# RoverWing-V4.net
KiCad netlist of a schematic drawn in EAGLE
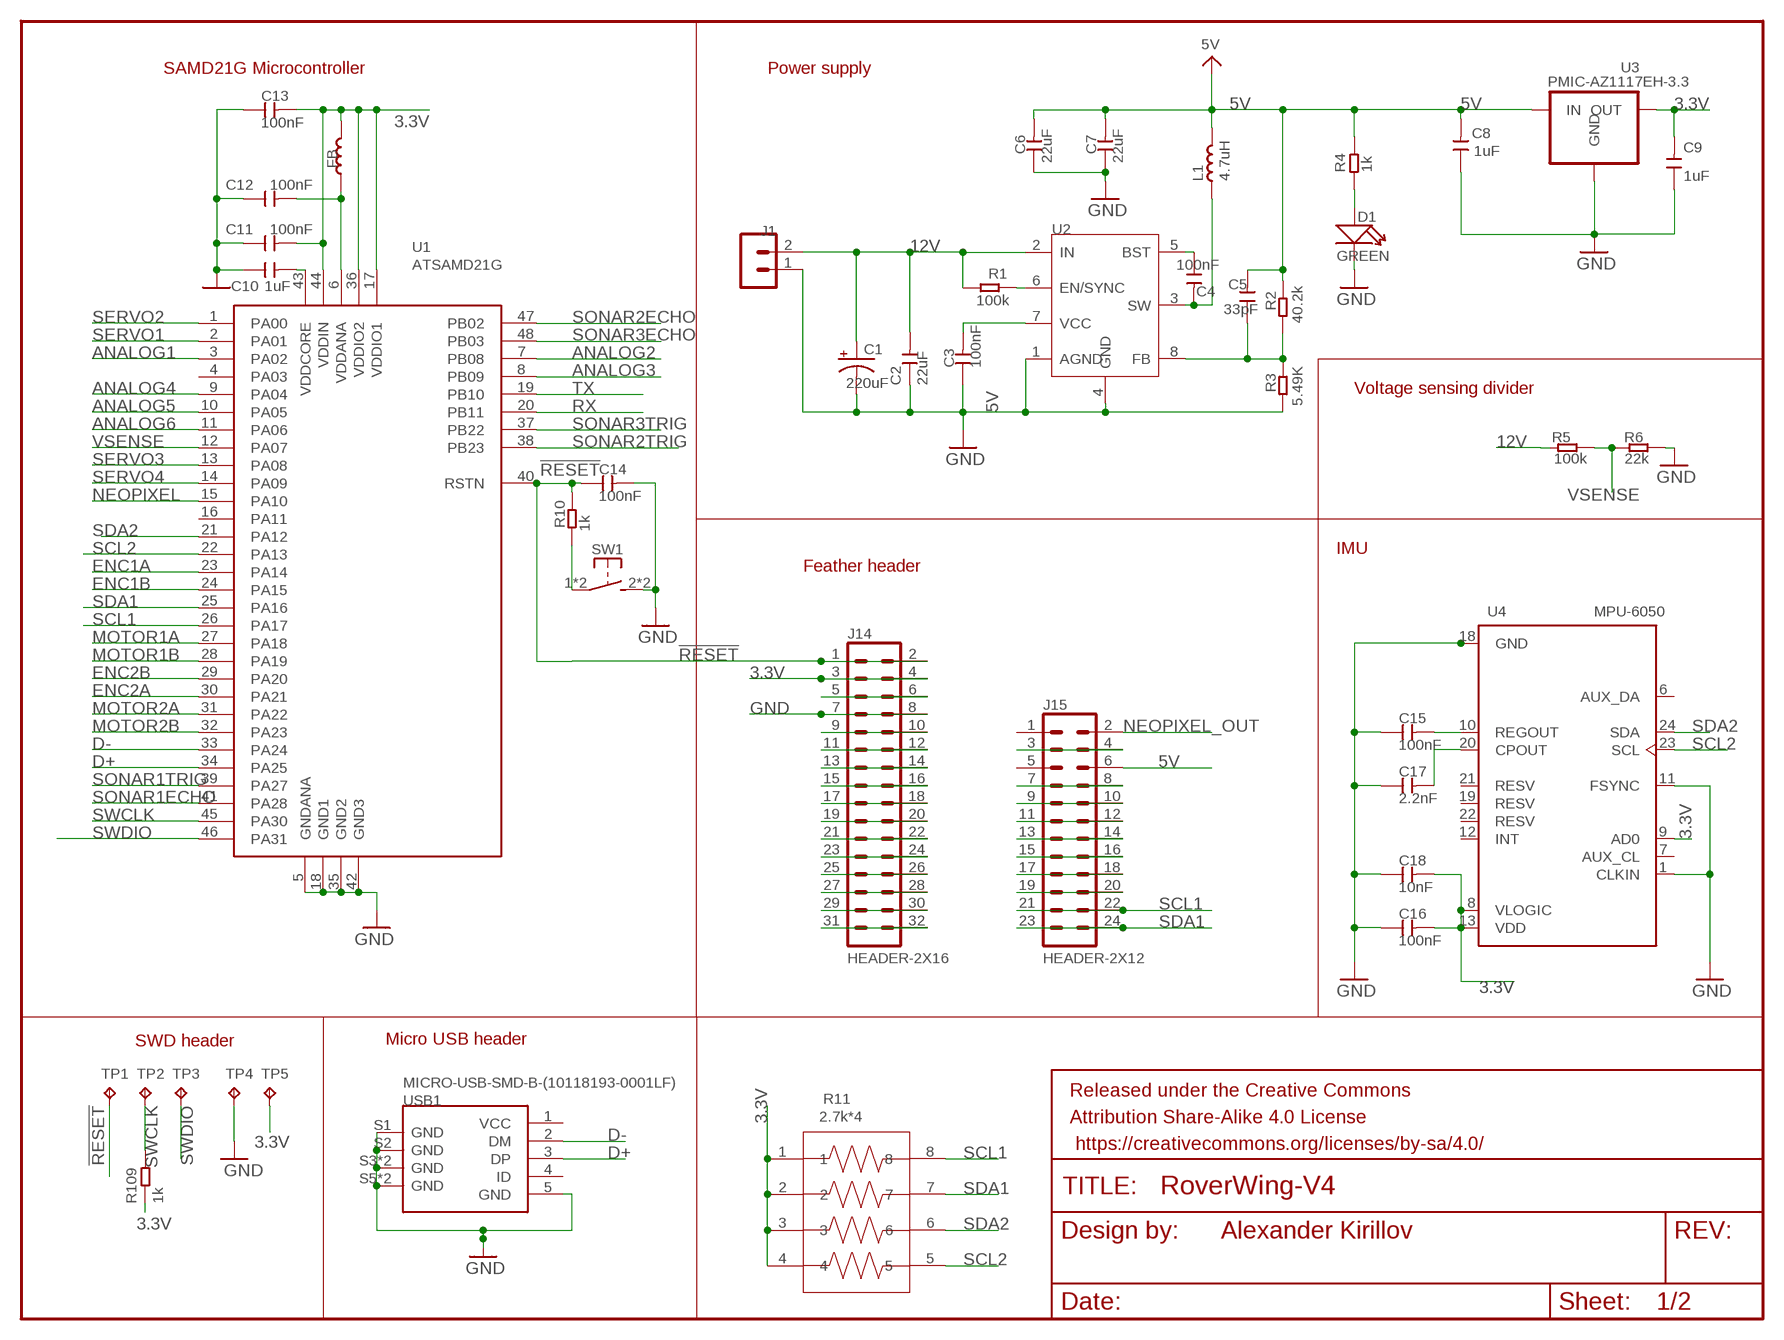
[diagram p0: schematic, sheet 1]
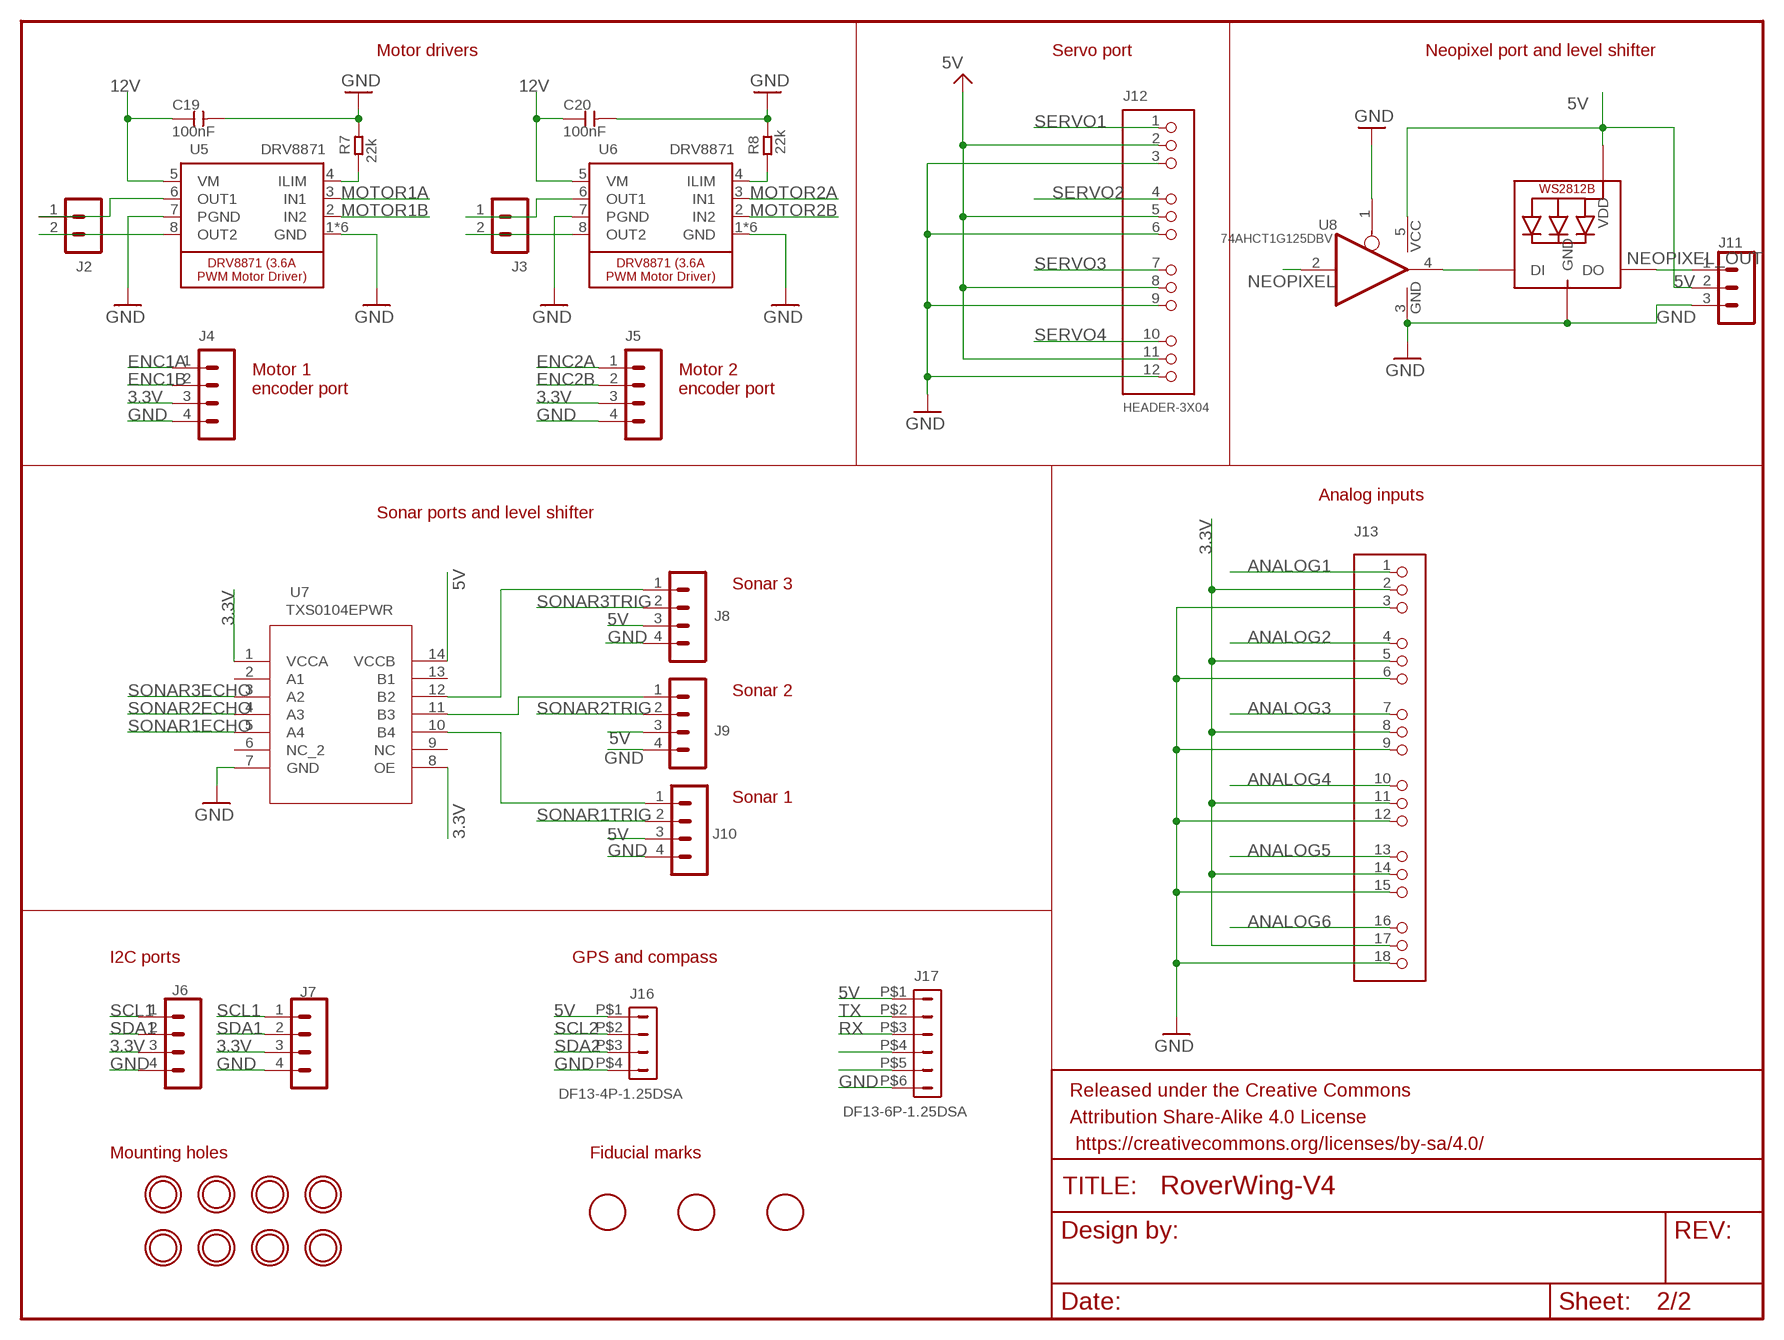
[diagram p1: schematic, sheet 2]

(export (version "E")
  (design (tool "Eeschema 10.0.6"))
  (components
    (comp (ref "C19")
      (value "100nF")
      (footprint "eagle-import:0805")
      (libsource (lib "eagle-import") (part "CAP-CERAMIC-SMD0805"))
    )
    (comp (ref "C20")
      (value "100nF")
      (footprint "eagle-import:0805")
      (libsource (lib "eagle-import") (part "CAP-CERAMIC-SMD0805"))
    )
    (comp (ref "FRAME1")
      (value "FRAME-LETTERNO_PACKAGE")
      (footprint "eagle-import:DUMMY")
      (libsource (lib "eagle-import") (part "FRAME-LETTERNO_PACKAGE"))
    )
    (comp (ref "J2")
      (value "HEADER-VH")
      (footprint "eagle-import:B2P-VH")
      (fields (field (name "PARTNO") "B2P-VH(LF)(SN)  "))
      (libsource (lib "eagle-import") (part "HEADER-VH"))
    )
    (comp (ref "J3")
      (value "HEADER-VH")
      (footprint "eagle-import:B2P-VH")
      (fields (field (name "PARTNO") "B2P-VH(LF)(SN)  "))
      (libsource (lib "eagle-import") (part "HEADER-VH"))
    )
    (comp (ref "J4")
      (value "HEADER-PH-4P")
      (footprint "eagle-import:B4B-PH-K")
      (fields (field (name "PARTNO") "B4B-PH-K-S(LF)(SN)"))
      (libsource (lib "eagle-import") (part "HEADER-PH-4P"))
    )
    (comp (ref "J5")
      (value "HEADER-PH-4P")
      (footprint "eagle-import:B4B-PH-K")
      (fields (field (name "PARTNO") "B4B-PH-K-S(LF)(SN)"))
      (libsource (lib "eagle-import") (part "HEADER-PH-4P"))
    )
    (comp (ref "J6")
      (value "HEADER-PH-4P")
      (footprint "eagle-import:B4B-PH-K")
      (fields (field (name "PARTNO") "B4B-PH-K-S(LF)(SN)"))
      (libsource (lib "eagle-import") (part "HEADER-PH-4P"))
    )
    (comp (ref "J7")
      (value "HEADER-PH-4P")
      (footprint "eagle-import:B4B-PH-K")
      (fields (field (name "PARTNO") "B4B-PH-K-S(LF)(SN)"))
      (libsource (lib "eagle-import") (part "HEADER-PH-4P"))
    )
    (comp (ref "J8")
      (value "HEADER-PH-4P")
      (footprint "eagle-import:B4B-PH-K")
      (fields (field (name "PARTNO") "B4B-PH-K-S(LF)(SN)"))
      (libsource (lib "eagle-import") (part "HEADER-PH-4P"))
    )
    (comp (ref "J9")
      (value "HEADER-PH-4P")
      (footprint "eagle-import:B4B-PH-K")
      (fields (field (name "PARTNO") "B4B-PH-K-S(LF)(SN)"))
      (libsource (lib "eagle-import") (part "HEADER-PH-4P"))
    )
    (comp (ref "J10")
      (value "HEADER-PH-4P")
      (footprint "eagle-import:B4B-PH-K")
      (fields (field (name "PARTNO") "B4B-PH-K-S(LF)(SN)"))
      (libsource (lib "eagle-import") (part "HEADER-PH-4P"))
    )
    (comp (ref "J11")
      (value "HEADER-PH-3P")
      (footprint "eagle-import:B3B-PH-K")
      (fields (field (name "PARTNO") "B3B-PH-K-S(LF)(SN)"))
      (libsource (lib "eagle-import") (part "HEADER-PH-3P"))
    )
    (comp (ref "J12")
      (value "HEADER-3X04")
      (footprint "eagle-import:3X04")
      (libsource (lib "eagle-import") (part "HEADER-3X04"))
    )
    (comp (ref "J13")
      (value "HEADER-3X06\"")
      (footprint "eagle-import:3X06")
      (libsource (lib "eagle-import") (part "HEADER-3X06{dblquote}"))
    )
    (comp (ref "J16")
      (value "DF13-4P-1.25DSA")
      (footprint "eagle-import:DF13-4P-1.25DSA")
      (libsource (lib "eagle-import") (part "DF13-4P-1.25DSA"))
    )
    (comp (ref "J17")
      (value "DF13-6P-1.25DSA")
      (footprint "eagle-import:DF13-6P-1.25DSA")
      (libsource (lib "eagle-import") (part "DF13-6P-1.25DSA"))
    )
    (comp (ref "LED1")
      (value "WS2812B3535")
      (footprint "eagle-import:LED3535")
      (fields (field (name "MANUFACTURER") "Worldsemi") (field (name "PARTNO") "WS2812B-3535 "))
      (libsource (lib "eagle-import") (part "WS2812B3535"))
    )
    (comp (ref "R7")
      (value "22k")
      (footprint "eagle-import:0805")
      (libsource (lib "eagle-import") (part "RES-SMD-0805"))
    )
    (comp (ref "R8")
      (value "22k")
      (footprint "eagle-import:0805")
      (libsource (lib "eagle-import") (part "RES-SMD-0805"))
    )
    (comp (ref "U$3")
      (value "MOUNTINGHOLE3.0_NPH")
      (footprint "eagle-import:MOUNTINGHOLE_3.0_NPH")
      (libsource (lib "eagle-import") (part "MOUNTINGHOLE3.0_NPH"))
    )
    (comp (ref "U$4")
      (value "MOUNTINGHOLE3.0_NPH")
      (footprint "eagle-import:MOUNTINGHOLE_3.0_NPH")
      (libsource (lib "eagle-import") (part "MOUNTINGHOLE3.0_NPH"))
    )
    (comp (ref "U$11")
      (value "FIDUCIAL")
      (footprint "eagle-import:FIDUCIAL_1MM")
      (libsource (lib "eagle-import") (part "FIDUCIAL"))
    )
    (comp (ref "U$13")
      (value "FIDUCIAL")
      (footprint "eagle-import:FIDUCIAL_1MM")
      (libsource (lib "eagle-import") (part "FIDUCIAL"))
    )
    (comp (ref "U$14")
      (value "MOUNTINGHOLE3.0_NPH")
      (footprint "eagle-import:MOUNTINGHOLE_3.0_NPH")
      (libsource (lib "eagle-import") (part "MOUNTINGHOLE3.0_NPH"))
    )
    (comp (ref "U$15")
      (value "MOUNTINGHOLE3.0_NPH")
      (footprint "eagle-import:MOUNTINGHOLE_3.0_NPH")
      (libsource (lib "eagle-import") (part "MOUNTINGHOLE3.0_NPH"))
    )
    (comp (ref "U$17")
      (value "FIDUCIAL")
      (footprint "eagle-import:FIDUCIAL_1MM")
      (libsource (lib "eagle-import") (part "FIDUCIAL"))
    )
    (comp (ref "U$24")
      (value "MOUNTINGHOLE3.0_NPH")
      (footprint "eagle-import:MOUNTINGHOLE_3.0_NPH")
      (libsource (lib "eagle-import") (part "MOUNTINGHOLE3.0_NPH"))
    )
    (comp (ref "U$25")
      (value "MOUNTINGHOLE3.0_NPH")
      (footprint "eagle-import:MOUNTINGHOLE_3.0_NPH")
      (libsource (lib "eagle-import") (part "MOUNTINGHOLE3.0_NPH"))
    )
    (comp (ref "U$26")
      (value "MOUNTINGHOLE3.0_NPH")
      (footprint "eagle-import:MOUNTINGHOLE_3.0_NPH")
      (libsource (lib "eagle-import") (part "MOUNTINGHOLE3.0_NPH"))
    )
    (comp (ref "U$27")
      (value "MOUNTINGHOLE3.0_NPH")
      (footprint "eagle-import:MOUNTINGHOLE_3.0_NPH")
      (libsource (lib "eagle-import") (part "MOUNTINGHOLE3.0_NPH"))
    )
    (comp (ref "U5")
      (value "DRV8871")
      (footprint "eagle-import:HSOP8")
      (fields (field (name "MANUFACTURER") "TEXAS INSTRUMENTS") (field (name "PARTNO") "DRV8871DDAR"))
      (libsource (lib "eagle-import") (part "DRV8871"))
    )
    (comp (ref "U6")
      (value "DRV8871")
      (footprint "eagle-import:HSOP8")
      (fields (field (name "MANUFACTURER") "TEXAS INSTRUMENTS") (field (name "PARTNO") "DRV8871DDAR"))
      (libsource (lib "eagle-import") (part "DRV8871"))
    )
    (comp (ref "U7")
      (value "TXS0104EPWR")
      (footprint "eagle-import:PW14")
      (fields (field (name "MANUFACTURER") "Texas Instruments"))
      (libsource (lib "eagle-import") (part "TXS0104EPWR"))
    )
    (comp (ref "U8")
      (value "74AHCT1G125DBV")
      (footprint "eagle-import:SOT23-5")
      (fields (field (name "PARTNO") "SN74AHCT1G125DBVR"))
      (libsource (lib "eagle-import") (part "741G125DBVAHCT"))
    )
    (comp (ref "C1")
      (value "220uF")
      (footprint "eagle-import:CAP-8X10.5")
      (libsource (lib "eagle-import") (part "CAP-POL-SMD-8X10.5"))
    )
    (comp (ref "C2")
      (value "22uF")
      (footprint "eagle-import:0805")
      (libsource (lib "eagle-import") (part "CAP-CERAMIC-SMD0805"))
    )
    (comp (ref "C3")
      (value "100nF")
      (footprint "eagle-import:0805")
      (libsource (lib "eagle-import") (part "CAP-CERAMIC-SMD0805"))
    )
    (comp (ref "C4")
      (value "100nF")
      (footprint "eagle-import:0805")
      (libsource (lib "eagle-import") (part "CAP-CERAMIC-SMD0805"))
    )
    (comp (ref "C5")
      (value "33pF")
      (footprint "eagle-import:0805")
      (libsource (lib "eagle-import") (part "CAP-CERAMIC-SMD0805"))
    )
    (comp (ref "C6")
      (value "22uF")
      (footprint "eagle-import:0805")
      (libsource (lib "eagle-import") (part "CAP-CERAMIC-SMD0805"))
    )
    (comp (ref "C7")
      (value "22uF")
      (footprint "eagle-import:0805")
      (libsource (lib "eagle-import") (part "CAP-CERAMIC-SMD0805"))
    )
    (comp (ref "C8")
      (value "1uF")
      (footprint "eagle-import:0805")
      (libsource (lib "eagle-import") (part "CAP-CERAMIC-SMD0805"))
    )
    (comp (ref "C9")
      (value "1uF")
      (footprint "eagle-import:0805")
      (libsource (lib "eagle-import") (part "CAP-CERAMIC-SMD0805"))
    )
    (comp (ref "C10")
      (value "1uF")
      (footprint "eagle-import:0805")
      (libsource (lib "eagle-import") (part "CAP-CERAMIC-SMD0805"))
    )
    (comp (ref "C11")
      (value "100nF")
      (footprint "eagle-import:0805")
      (libsource (lib "eagle-import") (part "CAP-CERAMIC-SMD0805"))
    )
    (comp (ref "C12")
      (value "100nF")
      (footprint "eagle-import:0805")
      (libsource (lib "eagle-import") (part "CAP-CERAMIC-SMD0805"))
    )
    (comp (ref "C13")
      (value "100nF")
      (footprint "eagle-import:0805")
      (libsource (lib "eagle-import") (part "CAP-CERAMIC-SMD0805"))
    )
    (comp (ref "C14")
      (value "100nF")
      (footprint "eagle-import:0805")
      (libsource (lib "eagle-import") (part "CAP-CERAMIC-SMD0805"))
    )
    (comp (ref "C15")
      (value "100nF")
      (footprint "eagle-import:0805")
      (libsource (lib "eagle-import") (part "CAP-CERAMIC-SMD0805"))
    )
    (comp (ref "C16")
      (value "100nF")
      (footprint "eagle-import:0805")
      (libsource (lib "eagle-import") (part "CAP-CERAMIC-SMD0805"))
    )
    (comp (ref "C17")
      (value "2.2nF")
      (footprint "eagle-import:0805")
      (libsource (lib "eagle-import") (part "CAP-CERAMIC-SMD0805"))
    )
    (comp (ref "C18")
      (value "10nF")
      (footprint "eagle-import:0805")
      (libsource (lib "eagle-import") (part "CAP-CERAMIC-SMD0805"))
    )
    (comp (ref "D1")
      (value "GREEN")
      (footprint "eagle-import:LED-0805")
      (libsource (lib "eagle-import") (part "SMD-LED-0805"))
    )
    (comp (ref "FB")
      (value "330R-1500MA")
      (footprint "eagle-import:0805")
      (fields (field (name "PARTNO") "BLM21PG331SN1D"))
      (libsource (lib "eagle-import") (part "SMD-FERRITE-BEAD-330R-1500MA(0805)"))
    )
    (comp (ref "FRAME2")
      (value "FRAME-LETTERNO_PACKAGE")
      (footprint "eagle-import:DUMMY")
      (libsource (lib "eagle-import") (part "FRAME-LETTERNO_PACKAGE"))
    )
    (comp (ref "J1")
      (value "HEADER-VH")
      (footprint "eagle-import:B2P-VH")
      (fields (field (name "PARTNO") "B2P-VH(LF)(SN)  "))
      (libsource (lib "eagle-import") (part "HEADER-VH"))
    )
    (comp (ref "J14")
      (value "HEADER-2X16")
      (footprint "eagle-import:2X16")
      (libsource (lib "eagle-import") (part "HEADER-2X16"))
    )
    (comp (ref "J15")
      (value "HEADER-2X12")
      (footprint "eagle-import:2X12")
      (libsource (lib "eagle-import") (part "HEADER-2X12"))
    )
    (comp (ref "L1")
      (value "4.7uH")
      (footprint "eagle-import:IND_TDK_7.1X6.5")
      (fields (field (name "MANUFACTURER") "TDK") (field (name "PARTNO") "SPM6530T-4R7M "))
      (libsource (lib "eagle-import") (part "IND-TDK-SPM6530T"))
    )
    (comp (ref "R1")
      (value "100k")
      (footprint "eagle-import:0805")
      (libsource (lib "eagle-import") (part "RES-SMD-0805"))
    )
    (comp (ref "R2")
      (value "40.2k")
      (footprint "eagle-import:0805")
      (libsource (lib "eagle-import") (part "RES-SMD-0805"))
    )
    (comp (ref "R3")
      (value "5.49K")
      (footprint "eagle-import:0805")
      (libsource (lib "eagle-import") (part "RES-SMD-0805"))
    )
    (comp (ref "R4")
      (value "1k")
      (footprint "eagle-import:0805")
      (libsource (lib "eagle-import") (part "RES-SMD-0805"))
    )
    (comp (ref "R5")
      (value "100k")
      (footprint "eagle-import:0805")
      (libsource (lib "eagle-import") (part "RES-SMD-0805"))
    )
    (comp (ref "R6")
      (value "22k")
      (footprint "eagle-import:0805")
      (libsource (lib "eagle-import") (part "RES-SMD-0805"))
    )
    (comp (ref "R10")
      (value "1k")
      (footprint "eagle-import:0805")
      (libsource (lib "eagle-import") (part "RES-SMD-0805"))
    )
    (comp (ref "R11")
      (value "2.7k*4")
      (footprint "eagle-import:0603_4")
      (fields (field (name "PARTNO") "RTA03-4D272JTP "))
      (libsource (lib "eagle-import") (part "RES_ARRAY-2.7KX40603X4"))
    )
    (comp (ref "R109")
      (value "1k")
      (footprint "eagle-import:0805")
      (libsource (lib "eagle-import") (part "RES-SMD-0805"))
    )
    (comp (ref "SW1")
      (value "SW-TACTILE-4.5X4.5_SMD")
      (footprint "eagle-import:TL3305")
      (fields (field (name "MANUFACTURER") "BRIGHT") (field (name "PARTNO") "TSA453G38-250 "))
      (libsource (lib "eagle-import") (part "SW-TACTILE-4.5X4.5_SMD"))
    )
    (comp (ref "TP1")
      (value "TPTP15R")
      (footprint "eagle-import:TP15R")
      (libsource (lib "eagle-import") (part "TPTP15R"))
    )
    (comp (ref "TP2")
      (value "TPTP15R")
      (footprint "eagle-import:TP15R")
      (libsource (lib "eagle-import") (part "TPTP15R"))
    )
    (comp (ref "TP3")
      (value "TPTP15R")
      (footprint "eagle-import:TP15R")
      (libsource (lib "eagle-import") (part "TPTP15R"))
    )
    (comp (ref "TP4")
      (value "TPTP15R")
      (footprint "eagle-import:TP15R")
      (libsource (lib "eagle-import") (part "TPTP15R"))
    )
    (comp (ref "TP5")
      (value "TPTP15R")
      (footprint "eagle-import:TP15R")
      (libsource (lib "eagle-import") (part "TPTP15R"))
    )
    (comp (ref "U1")
      (value "ATSAMD21G")
      (footprint "eagle-import:TQFP-48-EDITED")
      (fields (field (name "MANUFACTURER") "Microchip Technology") (field (name "PARTNO") "ATSAMD21G18A-AU"))
      (libsource (lib "eagle-import") (part "ATSAMD21G"))
    )
    (comp (ref "U2")
      (value "MP2225")
      (footprint "eagle-import:SOT-23-8")
      (fields (field (name "MANUFACTURER") "Monolithic Power Systems") (field (name "PARTNO") "MP2225GJ"))
      (libsource (lib "eagle-import") (part "PMIC-MP2225"))
    )
    (comp (ref "U3")
      (value "PMIC-AZ1117EH-3.3")
      (footprint "eagle-import:SOT223")
      (fields (field (name "PARTNO") "AZ1117EH-3.3TRG1"))
      (libsource (lib "eagle-import") (part "PMIC-AZ1117EH-3.3"))
    )
    (comp (ref "U4")
      (value "MPU-6050")
      (footprint "eagle-import:QFN50P400X400X95-24N")
      (fields (field (name "MANUFACTURER") "TDK InvenSense"))
      (libsource (lib "eagle-import") (part "MPU-6050"))
    )
    (comp (ref "USB1")
      (value "MICRO-USB-SMD-B-(10118193-0001LF)")
      (footprint "eagle-import:MICRO-USB5+6P-SMD-0.65-B")
      (fields (field (name "MANUFACTURER") "Amphenol ICC") (field (name "PARTNO") "10118193-0001LF"))
      (libsource (lib "eagle-import") (part "MICRO-USB-SMD-B-(10118193-0001LF)"))
    )
  )
  (nets
    (net (code "1") (name "3.3V") (class "Default")
      (node (ref "C11") (pin "2") (pinfunction "2_2") (pintype "passive"))
      (node (ref "C13") (pin "2") (pinfunction "2_2") (pintype "passive"))
      (node (ref "C16") (pin "2") (pinfunction "2_2") (pintype "passive"))
      (node (ref "C18") (pin "2") (pinfunction "2_2") (pintype "passive"))
      (node (ref "C9") (pin "2") (pinfunction "2_2") (pintype "passive"))
      (node (ref "FB") (pin "2") (pinfunction "2_2") (pintype "passive"))
      (node (ref "J13") (pin "11") (pinfunction "11_11") (pintype "passive"))
      (node (ref "J13") (pin "14") (pinfunction "14_14") (pintype "passive"))
      (node (ref "J13") (pin "17") (pinfunction "17_17") (pintype "passive"))
      (node (ref "J13") (pin "2") (pinfunction "2_2") (pintype "passive"))
      (node (ref "J13") (pin "5") (pinfunction "5_5") (pintype "passive"))
      (node (ref "J13") (pin "8") (pinfunction "8_8") (pintype "passive"))
      (node (ref "J14") (pin "3") (pinfunction "3_3") (pintype "passive"))
      (node (ref "J14") (pin "4") (pinfunction "4_4") (pintype "passive"))
      (node (ref "J4") (pin "3") (pinfunction "3_3") (pintype "passive"))
      (node (ref "J5") (pin "3") (pinfunction "3_3") (pintype "passive"))
      (node (ref "J6") (pin "3") (pinfunction "3_3") (pintype "passive"))
      (node (ref "J7") (pin "3") (pinfunction "3_3") (pintype "passive"))
      (node (ref "R109") (pin "1") (pinfunction "1_1") (pintype "passive"))
      (node (ref "R11") (pin "1") (pinfunction "1_1") (pintype "passive"))
      (node (ref "R11") (pin "2") (pinfunction "2_2") (pintype "passive"))
      (node (ref "R11") (pin "3") (pinfunction "3_3") (pintype "passive"))
      (node (ref "R11") (pin "4") (pinfunction "4_4") (pintype "passive"))
      (node (ref "TP5") (pin "TP") (pinfunction "TP_TP") (pintype "input"))
      (node (ref "U1") (pin "17") (pinfunction "VDDIO1_17") (pintype "power_in"))
      (node (ref "U1") (pin "36") (pinfunction "VDDIO2_36") (pintype "power_in"))
      (node (ref "U1") (pin "44") (pinfunction "VDDIN_44") (pintype "power_in"))
      (node (ref "U3") (pin "2") (pinfunction "OUT_2") (pintype "output"))
      (node (ref "U3") (pin "4") (pinfunction "OUT_4") (pintype "output"))
      (node (ref "U4") (pin "13") (pinfunction "VDD_13") (pintype "power_in"))
      (node (ref "U4") (pin "8") (pinfunction "VLOGIC_8") (pintype "power_in"))
      (node (ref "U4") (pin "9") (pinfunction "AD0_9") (pintype "input"))
      (node (ref "U7") (pin "1") (pinfunction "VCCA_1") (pintype "power_in"))
      (node (ref "U7") (pin "8") (pinfunction "OE_8") (pintype "output"))
    )
    (net (code "2") (name "5V") (class "Default")
      (node (ref "C5") (pin "2") (pinfunction "2_2") (pintype "passive"))
      (node (ref "C6") (pin "2") (pinfunction "2_2") (pintype "passive"))
      (node (ref "C7") (pin "2") (pinfunction "2_2") (pintype "passive"))
      (node (ref "C8") (pin "2") (pinfunction "2_2") (pintype "passive"))
      (node (ref "J10") (pin "3") (pinfunction "3_3") (pintype "passive"))
      (node (ref "J11") (pin "2") (pinfunction "2_2") (pintype "passive"))
      (node (ref "J12") (pin "11") (pinfunction "11_11") (pintype "passive"))
      (node (ref "J12") (pin "2") (pinfunction "2_2") (pintype "passive"))
      (node (ref "J12") (pin "5") (pinfunction "5_5") (pintype "passive"))
      (node (ref "J12") (pin "8") (pinfunction "8_8") (pintype "passive"))
      (node (ref "J15") (pin "6") (pinfunction "6_6") (pintype "passive"))
      (node (ref "J16") (pin "P$1") (pinfunction "1_P$1") (pintype "passive"))
      (node (ref "J17") (pin "P$1") (pinfunction "1_P$1") (pintype "passive"))
      (node (ref "J8") (pin "3") (pinfunction "3_3") (pintype "passive"))
      (node (ref "J9") (pin "3") (pinfunction "3_3") (pintype "passive"))
      (node (ref "L1") (pin "2") (pinfunction "2_2") (pintype "passive"))
      (node (ref "LED1") (pin "2") (pinfunction "VDD_2") (pintype "power_in"))
      (node (ref "R2") (pin "1") (pinfunction "1_1") (pintype "passive"))
      (node (ref "R4") (pin "2") (pinfunction "2_2") (pintype "passive"))
      (node (ref "U3") (pin "3") (pinfunction "IN_3") (pintype "input"))
      (node (ref "U7") (pin "14") (pinfunction "VCCB_14") (pintype "power_in"))
      (node (ref "U8") (pin "5") (pinfunction "VCC_5") (pintype "power_in"))
    )
    (net (code "3") (name "12V") (class "Default")
      (node (ref "C1") (pin "+") (pinfunction "+_+") (pintype "passive"))
      (node (ref "C19") (pin "1") (pinfunction "1_1") (pintype "passive"))
      (node (ref "C2") (pin "2") (pinfunction "2_2") (pintype "passive"))
      (node (ref "C20") (pin "1") (pinfunction "1_1") (pintype "passive"))
      (node (ref "J1") (pin "2") (pinfunction "2_2") (pintype "passive"))
      (node (ref "R1") (pin "2") (pinfunction "2_2") (pintype "passive"))
      (node (ref "R5") (pin "2") (pinfunction "2_2") (pintype "passive"))
      (node (ref "U2") (pin "2") (pinfunction "IN_2") (pintype "bidirectional"))
      (node (ref "U5") (pin "5") (pinfunction "VM_5") (pintype "power_in"))
      (node (ref "U6") (pin "5") (pinfunction "VM_5") (pintype "power_in"))
    )
    (net (code "4") (name "ANALOG1") (class "Default")
      (node (ref "J13") (pin "1") (pinfunction "1_1") (pintype "passive"))
      (node (ref "U1") (pin "3") (pinfunction "PA02_3") (pintype "bidirectional"))
    )
    (net (code "5") (name "ANALOG2") (class "Default")
      (node (ref "J13") (pin "4") (pinfunction "4_4") (pintype "passive"))
      (node (ref "U1") (pin "7") (pinfunction "PB08_7") (pintype "bidirectional"))
    )
    (net (code "6") (name "ANALOG3") (class "Default")
      (node (ref "J13") (pin "7") (pinfunction "7_7") (pintype "passive"))
      (node (ref "U1") (pin "8") (pinfunction "PB09_8") (pintype "bidirectional"))
    )
    (net (code "7") (name "ANALOG4") (class "Default")
      (node (ref "J13") (pin "10") (pinfunction "10_10") (pintype "passive"))
      (node (ref "U1") (pin "9") (pinfunction "PA04_9") (pintype "bidirectional"))
    )
    (net (code "8") (name "ANALOG5") (class "Default")
      (node (ref "J13") (pin "13") (pinfunction "13_13") (pintype "passive"))
      (node (ref "U1") (pin "10") (pinfunction "PA05_10") (pintype "bidirectional"))
    )
    (net (code "9") (name "ANALOG6") (class "Default")
      (node (ref "J13") (pin "16") (pinfunction "16_16") (pintype "passive"))
      (node (ref "U1") (pin "11") (pinfunction "PA06_11") (pintype "bidirectional"))
    )
    (net (code "10") (name "D+") (class "Default")
      (node (ref "U1") (pin "34") (pinfunction "PA25_34") (pintype "bidirectional"))
      (node (ref "USB1") (pin "3") (pinfunction "DP_3") (pintype "bidirectional"))
    )
    (net (code "11") (name "D-") (class "Default")
      (node (ref "U1") (pin "33") (pinfunction "PA24_33") (pintype "bidirectional"))
      (node (ref "USB1") (pin "2") (pinfunction "DM_2") (pintype "bidirectional"))
    )
    (net (code "12") (name "ENC1A") (class "Default")
      (node (ref "J4") (pin "1") (pinfunction "1_1") (pintype "passive"))
      (node (ref "U1") (pin "23") (pinfunction "PA14_23") (pintype "bidirectional"))
    )
    (net (code "13") (name "ENC1B") (class "Default")
      (node (ref "J4") (pin "2") (pinfunction "2_2") (pintype "passive"))
      (node (ref "U1") (pin "24") (pinfunction "PA15_24") (pintype "bidirectional"))
    )
    (net (code "14") (name "ENC2A") (class "Default")
      (node (ref "J5") (pin "1") (pinfunction "1_1") (pintype "passive"))
      (node (ref "U1") (pin "30") (pinfunction "PA21_30") (pintype "bidirectional"))
    )
    (net (code "15") (name "ENC2B") (class "Default")
      (node (ref "J5") (pin "2") (pinfunction "2_2") (pintype "passive"))
      (node (ref "U1") (pin "29") (pinfunction "PA20_29") (pintype "bidirectional"))
    )
    (net (code "16") (name "GND") (class "Default")
      (node (ref "C1") (pin "-") (pinfunction "-_-") (pintype "passive"))
      (node (ref "C10") (pin "1") (pinfunction "1_1") (pintype "passive"))
      (node (ref "C11") (pin "1") (pinfunction "1_1") (pintype "passive"))
      (node (ref "C12") (pin "1") (pinfunction "1_1") (pintype "passive"))
      (node (ref "C13") (pin "1") (pinfunction "1_1") (pintype "passive"))
      (node (ref "C14") (pin "2") (pinfunction "2_2") (pintype "passive"))
      (node (ref "C15") (pin "1") (pinfunction "1_1") (pintype "passive"))
      (node (ref "C16") (pin "1") (pinfunction "1_1") (pintype "passive"))
      (node (ref "C17") (pin "1") (pinfunction "1_1") (pintype "passive"))
      (node (ref "C18") (pin "1") (pinfunction "1_1") (pintype "passive"))
      (node (ref "C19") (pin "2") (pinfunction "2_2") (pintype "passive"))
      (node (ref "C2") (pin "1") (pinfunction "1_1") (pintype "passive"))
      (node (ref "C20") (pin "2") (pinfunction "2_2") (pintype "passive"))
      (node (ref "C3") (pin "1") (pinfunction "1_1") (pintype "passive"))
      (node (ref "C6") (pin "1") (pinfunction "1_1") (pintype "passive"))
      (node (ref "C7") (pin "1") (pinfunction "1_1") (pintype "passive"))
      (node (ref "C8") (pin "1") (pinfunction "1_1") (pintype "passive"))
      (node (ref "C9") (pin "1") (pinfunction "1_1") (pintype "passive"))
      (node (ref "D1") (pin "-") (pinfunction "-_-") (pintype "passive"))
      (node (ref "J1") (pin "1") (pinfunction "1_1") (pintype "passive"))
      (node (ref "J10") (pin "4") (pinfunction "4_4") (pintype "passive"))
      (node (ref "J11") (pin "3") (pinfunction "3_3") (pintype "passive"))
      (node (ref "J12") (pin "12") (pinfunction "12_12") (pintype "passive"))
      (node (ref "J12") (pin "3") (pinfunction "3_3") (pintype "passive"))
      (node (ref "J12") (pin "6") (pinfunction "6_6") (pintype "passive"))
      (node (ref "J12") (pin "9") (pinfunction "9_9") (pintype "passive"))
      (node (ref "J13") (pin "12") (pinfunction "12_12") (pintype "passive"))
      (node (ref "J13") (pin "15") (pinfunction "15_15") (pintype "passive"))
      (node (ref "J13") (pin "18") (pinfunction "18_18") (pintype "passive"))
      (node (ref "J13") (pin "3") (pinfunction "3_3") (pintype "passive"))
      (node (ref "J13") (pin "6") (pinfunction "6_6") (pintype "passive"))
      (node (ref "J13") (pin "9") (pinfunction "9_9") (pintype "passive"))
      (node (ref "J14") (pin "7") (pinfunction "7_7") (pintype "passive"))
      (node (ref "J14") (pin "8") (pinfunction "8_8") (pintype "passive"))
      (node (ref "J16") (pin "P$4") (pinfunction "4_P$4") (pintype "passive"))
      (node (ref "J17") (pin "P$6") (pinfunction "6_P$6") (pintype "passive"))
      (node (ref "J4") (pin "4") (pinfunction "4_4") (pintype "passive"))
      (node (ref "J5") (pin "4") (pinfunction "4_4") (pintype "passive"))
      (node (ref "J6") (pin "4") (pinfunction "4_4") (pintype "passive"))
      (node (ref "J7") (pin "4") (pinfunction "4_4") (pintype "passive"))
      (node (ref "J8") (pin "4") (pinfunction "4_4") (pintype "passive"))
      (node (ref "J9") (pin "4") (pinfunction "4_4") (pintype "passive"))
      (node (ref "LED1") (pin "4") (pinfunction "GND_4") (pintype "power_in"))
      (node (ref "R3") (pin "2") (pinfunction "2_2") (pintype "passive"))
      (node (ref "R6") (pin "2") (pinfunction "2_2") (pintype "passive"))
      (node (ref "R7") (pin "2") (pinfunction "2_2") (pintype "passive"))
      (node (ref "R8") (pin "2") (pinfunction "2_2") (pintype "passive"))
      (node (ref "SW1") (pin "2") (pinfunction "S1_2") (pintype "passive"))
      (node (ref "SW1") (pin "3") (pinfunction "S1_3") (pintype "passive"))
      (node (ref "TP4") (pin "TP") (pinfunction "TP_TP") (pintype "input"))
      (node (ref "U1") (pin "18") (pinfunction "GND1_18") (pintype "power_in"))
      (node (ref "U1") (pin "35") (pinfunction "GND2_35") (pintype "power_in"))
      (node (ref "U1") (pin "42") (pinfunction "GND3_42") (pintype "power_in"))
      (node (ref "U1") (pin "5") (pinfunction "GNDANA_5") (pintype "power_in"))
      (node (ref "U2") (pin "1") (pinfunction "AGND_1") (pintype "bidirectional"))
      (node (ref "U2") (pin "4") (pinfunction "GND_4") (pintype "bidirectional"))
      (node (ref "U3") (pin "1") (pinfunction "GND_1") (pintype "power_in"))
      (node (ref "U4") (pin "1") (pinfunction "CLKIN_1") (pintype "input"))
      (node (ref "U4") (pin "11") (pinfunction "FSYNC_11") (pintype "input"))
      (node (ref "U4") (pin "18") (pinfunction "GND_18") (pintype "power_in"))
      (node (ref "U5") (pin "1") (pinfunction "GND_1") (pintype "power_in"))
      (node (ref "U5") (pin "7") (pinfunction "PGND_7") (pintype "power_in"))
      (node (ref "U5") (pin "GND") (pinfunction "GND_GND") (pintype "power_in"))
      (node (ref "U5") (pin "P$1") (pinfunction "GND_P$1") (pintype "power_in"))
      (node (ref "U5") (pin "P$2") (pinfunction "GND_P$2") (pintype "power_in"))
      (node (ref "U5") (pin "P$3") (pinfunction "GND_P$3") (pintype "power_in"))
      (node (ref "U5") (pin "P$4") (pinfunction "GND_P$4") (pintype "power_in"))
      (node (ref "U6") (pin "1") (pinfunction "GND_1") (pintype "power_in"))
      (node (ref "U6") (pin "7") (pinfunction "PGND_7") (pintype "power_in"))
      (node (ref "U6") (pin "GND") (pinfunction "GND_GND") (pintype "power_in"))
      (node (ref "U6") (pin "P$1") (pinfunction "GND_P$1") (pintype "power_in"))
      (node (ref "U6") (pin "P$2") (pinfunction "GND_P$2") (pintype "power_in"))
      (node (ref "U6") (pin "P$3") (pinfunction "GND_P$3") (pintype "power_in"))
      (node (ref "U6") (pin "P$4") (pinfunction "GND_P$4") (pintype "power_in"))
      (node (ref "U7") (pin "7") (pinfunction "GND_7") (pintype "power_in"))
      (node (ref "U8") (pin "1") (pinfunction "OE_1") (pintype "input"))
      (node (ref "U8") (pin "3") (pinfunction "GND_3") (pintype "power_in"))
      (node (ref "USB1") (pin "5") (pinfunction "GND_5") (pintype "bidirectional"))
      (node (ref "USB1") (pin "S1") (pinfunction "GND_S1") (pintype "bidirectional"))
      (node (ref "USB1") (pin "S2") (pinfunction "GND_S2") (pintype "bidirectional"))
      (node (ref "USB1") (pin "S3") (pinfunction "GND_S3") (pintype "bidirectional"))
      (node (ref "USB1") (pin "S4") (pinfunction "GND_S4") (pintype "bidirectional"))
      (node (ref "USB1") (pin "S5") (pinfunction "GND_S5") (pintype "bidirectional"))
      (node (ref "USB1") (pin "S6") (pinfunction "GND_S6") (pintype "bidirectional"))
    )
    (net (code "17") (name "MOTOR1A") (class "Default")
      (node (ref "U1") (pin "27") (pinfunction "PA18_27") (pintype "bidirectional"))
      (node (ref "U5") (pin "3") (pinfunction "IN1_3") (pintype "input"))
    )
    (net (code "18") (name "MOTOR1B") (class "Default")
      (node (ref "U1") (pin "28") (pinfunction "PA19_28") (pintype "bidirectional"))
      (node (ref "U5") (pin "2") (pinfunction "IN2_2") (pintype "input"))
    )
    (net (code "19") (name "MOTOR2A") (class "Default")
      (node (ref "U1") (pin "31") (pinfunction "PA22_31") (pintype "bidirectional"))
      (node (ref "U6") (pin "3") (pinfunction "IN1_3") (pintype "input"))
    )
    (net (code "20") (name "MOTOR2B") (class "Default")
      (node (ref "U1") (pin "32") (pinfunction "PA23_32") (pintype "bidirectional"))
      (node (ref "U6") (pin "2") (pinfunction "IN2_2") (pintype "input"))
    )
    (net (code "21") (name "NEOPIXEL") (class "Default")
      (node (ref "U1") (pin "15") (pinfunction "PA10_15") (pintype "bidirectional"))
      (node (ref "U8") (pin "2") (pinfunction "I_2") (pintype "input"))
    )
    (net (code "22") (name "NEOPIXEL_OUT") (class "Default")
      (node (ref "J11") (pin "1") (pinfunction "1_1") (pintype "passive"))
      (node (ref "J15") (pin "2") (pinfunction "2_2") (pintype "passive"))
      (node (ref "LED1") (pin "3") (pinfunction "DO_3") (pintype "output"))
    )
    (net (code "23") (name "Net-(D1-Pad+)") (class "Default")
      (node (ref "D1") (pin "+") (pinfunction "+_+") (pintype "passive"))
      (node (ref "R4") (pin "1") (pinfunction "1_1") (pintype "passive"))
    )
    (net (code "24") (name "Net-(J14-Pad5)") (class "Default")
      (node (ref "J14") (pin "5") (pinfunction "5_5") (pintype "passive"))
      (node (ref "J14") (pin "6") (pinfunction "6_6") (pintype "passive"))
    )
    (net (code "25") (name "Net-(J14-Pad10)") (class "Default")
      (node (ref "J14") (pin "10") (pinfunction "10_10") (pintype "passive"))
      (node (ref "J14") (pin "9") (pinfunction "9_9") (pintype "passive"))
    )
    (net (code "26") (name "Net-(J14-Pad11)") (class "Default")
      (node (ref "J14") (pin "11") (pinfunction "11_11") (pintype "passive"))
      (node (ref "J14") (pin "12") (pinfunction "12_12") (pintype "passive"))
    )
    (net (code "27") (name "Net-(J14-Pad13)") (class "Default")
      (node (ref "J14") (pin "13") (pinfunction "13_13") (pintype "passive"))
      (node (ref "J14") (pin "14") (pinfunction "14_14") (pintype "passive"))
    )
    (net (code "28") (name "Net-(J14-Pad15)") (class "Default")
      (node (ref "J14") (pin "15") (pinfunction "15_15") (pintype "passive"))
      (node (ref "J14") (pin "16") (pinfunction "16_16") (pintype "passive"))
    )
    (net (code "29") (name "Net-(J14-Pad17)") (class "Default")
      (node (ref "J14") (pin "17") (pinfunction "17_17") (pintype "passive"))
      (node (ref "J14") (pin "18") (pinfunction "18_18") (pintype "passive"))
    )
    (net (code "30") (name "Net-(J14-Pad19)") (class "Default")
      (node (ref "J14") (pin "19") (pinfunction "19_19") (pintype "passive"))
      (node (ref "J14") (pin "20") (pinfunction "20_20") (pintype "passive"))
    )
    (net (code "31") (name "Net-(J14-Pad21)") (class "Default")
      (node (ref "J14") (pin "21") (pinfunction "21_21") (pintype "passive"))
      (node (ref "J14") (pin "22") (pinfunction "22_22") (pintype "passive"))
    )
    (net (code "32") (name "Net-(J14-Pad23)") (class "Default")
      (node (ref "J14") (pin "23") (pinfunction "23_23") (pintype "passive"))
      (node (ref "J14") (pin "24") (pinfunction "24_24") (pintype "passive"))
    )
    (net (code "33") (name "Net-(J14-Pad25)") (class "Default")
      (node (ref "J14") (pin "25") (pinfunction "25_25") (pintype "passive"))
      (node (ref "J14") (pin "26") (pinfunction "26_26") (pintype "passive"))
    )
    (net (code "34") (name "Net-(J14-Pad27)") (class "Default")
      (node (ref "J14") (pin "27") (pinfunction "27_27") (pintype "passive"))
      (node (ref "J14") (pin "28") (pinfunction "28_28") (pintype "passive"))
    )
    (net (code "35") (name "Net-(J14-Pad29)") (class "Default")
      (node (ref "J14") (pin "29") (pinfunction "29_29") (pintype "passive"))
      (node (ref "J14") (pin "30") (pinfunction "30_30") (pintype "passive"))
    )
    (net (code "36") (name "Net-(J14-Pad31)") (class "Default")
      (node (ref "J14") (pin "31") (pinfunction "31_31") (pintype "passive"))
      (node (ref "J14") (pin "32") (pinfunction "32_32") (pintype "passive"))
    )
    (net (code "37") (name "Net-(J15-Pad3)") (class "Default")
      (node (ref "J15") (pin "3") (pinfunction "3_3") (pintype "passive"))
      (node (ref "J15") (pin "4") (pinfunction "4_4") (pintype "passive"))
    )
    (net (code "38") (name "Net-(J15-Pad7)") (class "Default")
      (node (ref "J15") (pin "7") (pinfunction "7_7") (pintype "passive"))
      (node (ref "J15") (pin "8") (pinfunction "8_8") (pintype "passive"))
    )
    (net (code "39") (name "Net-(J15-Pad10)") (class "Default")
      (node (ref "J15") (pin "10") (pinfunction "10_10") (pintype "passive"))
      (node (ref "J15") (pin "9") (pinfunction "9_9") (pintype "passive"))
    )
    (net (code "40") (name "Net-(J15-Pad11)") (class "Default")
      (node (ref "J15") (pin "11") (pinfunction "11_11") (pintype "passive"))
      (node (ref "J15") (pin "12") (pinfunction "12_12") (pintype "passive"))
    )
    (net (code "41") (name "Net-(J15-Pad13)") (class "Default")
      (node (ref "J15") (pin "13") (pinfunction "13_13") (pintype "passive"))
      (node (ref "J15") (pin "14") (pinfunction "14_14") (pintype "passive"))
    )
    (net (code "42") (name "Net-(J15-Pad15)") (class "Default")
      (node (ref "J15") (pin "15") (pinfunction "15_15") (pintype "passive"))
      (node (ref "J15") (pin "16") (pinfunction "16_16") (pintype "passive"))
    )
    (net (code "43") (name "Net-(J15-Pad17)") (class "Default")
      (node (ref "J15") (pin "17") (pinfunction "17_17") (pintype "passive"))
      (node (ref "J15") (pin "18") (pinfunction "18_18") (pintype "passive"))
    )
    (net (code "44") (name "Net-(J15-Pad19)") (class "Default")
      (node (ref "J15") (pin "19") (pinfunction "19_19") (pintype "passive"))
      (node (ref "J15") (pin "20") (pinfunction "20_20") (pintype "passive"))
    )
    (net (code "45") (name "Net-(LED1-DI)") (class "Default")
      (node (ref "LED1") (pin "1") (pinfunction "DI_1") (pintype "input"))
      (node (ref "U8") (pin "4") (pinfunction "O_4") (pintype "tri_state"))
    )
    (net (code "46") (name "Net-(R10-Pad1)") (class "Default")
      (node (ref "R10") (pin "1") (pinfunction "1_1") (pintype "passive"))
      (node (ref "SW1") (pin "1") (pinfunction "P1_1") (pintype "passive"))
      (node (ref "SW1") (pin "4") (pinfunction "P1_4") (pintype "passive"))
    )
    (net (code "47") (name "Net-(U1-VDDANA)") (class "Default")
      (node (ref "C12") (pin "2") (pinfunction "2_2") (pintype "passive"))
      (node (ref "FB") (pin "1") (pinfunction "1_1") (pintype "passive"))
      (node (ref "U1") (pin "6") (pinfunction "VDDANA_6") (pintype "power_in"))
    )
    (net (code "48") (name "Net-(U1-VDDCORE)") (class "Default")
      (node (ref "C10") (pin "2") (pinfunction "2_2") (pintype "passive"))
      (node (ref "U1") (pin "43") (pinfunction "VDDCORE_43") (pintype "power_in"))
    )
    (net (code "49") (name "Net-(U2-BST)") (class "Default")
      (node (ref "C4") (pin "1") (pinfunction "1_1") (pintype "passive"))
      (node (ref "U2") (pin "5") (pinfunction "BST_5") (pintype "bidirectional"))
    )
    (net (code "50") (name "Net-(U2-EN{slash}SYNC)") (class "Default")
      (node (ref "R1") (pin "1") (pinfunction "1_1") (pintype "passive"))
      (node (ref "U2") (pin "6") (pinfunction "EN/SYNC_6") (pintype "bidirectional"))
    )
    (net (code "51") (name "Net-(U2-FB)") (class "Default")
      (node (ref "C5") (pin "1") (pinfunction "1_1") (pintype "passive"))
      (node (ref "R2") (pin "2") (pinfunction "2_2") (pintype "passive"))
      (node (ref "R3") (pin "1") (pinfunction "1_1") (pintype "passive"))
      (node (ref "U2") (pin "8") (pinfunction "FB_8") (pintype "bidirectional"))
    )
    (net (code "52") (name "Net-(U2-SW)") (class "Default")
      (node (ref "C4") (pin "2") (pinfunction "2_2") (pintype "passive"))
      (node (ref "L1") (pin "1") (pinfunction "1_1") (pintype "passive"))
      (node (ref "U2") (pin "3") (pinfunction "SW_3") (pintype "bidirectional"))
    )
    (net (code "53") (name "Net-(U2-VCC)") (class "Default")
      (node (ref "C3") (pin "2") (pinfunction "2_2") (pintype "passive"))
      (node (ref "U2") (pin "7") (pinfunction "VCC_7") (pintype "bidirectional"))
    )
    (net (code "54") (name "Net-(U4-CPOUT)") (class "Default")
      (node (ref "C17") (pin "2") (pinfunction "2_2") (pintype "passive"))
      (node (ref "U4") (pin "20") (pinfunction "CPOUT_20") (pintype "passive"))
    )
    (net (code "55") (name "Net-(U4-REGOUT)") (class "Default")
      (node (ref "C15") (pin "2") (pinfunction "2_2") (pintype "passive"))
      (node (ref "U4") (pin "10") (pinfunction "REGOUT_10") (pintype "passive"))
    )
    (net (code "56") (name "Net-(U5-ILIM)") (class "Default")
      (node (ref "R7") (pin "1") (pinfunction "1_1") (pintype "passive"))
      (node (ref "U5") (pin "4") (pinfunction "ILIM_4") (pintype "input"))
    )
    (net (code "57") (name "Net-(U5-OUT1)") (class "Default")
      (node (ref "J2") (pin "1") (pinfunction "1_1") (pintype "passive"))
      (node (ref "U5") (pin "6") (pinfunction "OUT1_6") (pintype "output"))
    )
    (net (code "58") (name "Net-(U5-OUT2)") (class "Default")
      (node (ref "J2") (pin "2") (pinfunction "2_2") (pintype "passive"))
      (node (ref "U5") (pin "8") (pinfunction "OUT2_8") (pintype "output"))
    )
    (net (code "59") (name "Net-(U6-ILIM)") (class "Default")
      (node (ref "R8") (pin "1") (pinfunction "1_1") (pintype "passive"))
      (node (ref "U6") (pin "4") (pinfunction "ILIM_4") (pintype "input"))
    )
    (net (code "60") (name "Net-(U6-OUT1)") (class "Default")
      (node (ref "J3") (pin "1") (pinfunction "1_1") (pintype "passive"))
      (node (ref "U6") (pin "6") (pinfunction "OUT1_6") (pintype "output"))
    )
    (net (code "61") (name "Net-(U6-OUT2)") (class "Default")
      (node (ref "J3") (pin "2") (pinfunction "2_2") (pintype "passive"))
      (node (ref "U6") (pin "8") (pinfunction "OUT2_8") (pintype "output"))
    )
    (net (code "62") (name "Net-(U7-B2)") (class "Default")
      (node (ref "J8") (pin "1") (pinfunction "1_1") (pintype "passive"))
      (node (ref "U7") (pin "12") (pinfunction "B2_12") (pintype "bidirectional"))
    )
    (net (code "63") (name "Net-(U7-B3)") (class "Default")
      (node (ref "J9") (pin "1") (pinfunction "1_1") (pintype "passive"))
      (node (ref "U7") (pin "11") (pinfunction "B3_11") (pintype "bidirectional"))
    )
    (net (code "64") (name "Net-(U7-B4)") (class "Default")
      (node (ref "J10") (pin "1") (pinfunction "1_1") (pintype "passive"))
      (node (ref "U7") (pin "10") (pinfunction "B4_10") (pintype "bidirectional"))
    )
    (net (code "65") (name "RX") (class "Default")
      (node (ref "J17") (pin "P$3") (pinfunction "3_P$3") (pintype "passive"))
      (node (ref "U1") (pin "20") (pinfunction "PB11_20") (pintype "bidirectional"))
    )
    (net (code "66") (name "SCL1") (class "Default")
      (node (ref "J15") (pin "21") (pinfunction "21_21") (pintype "passive"))
      (node (ref "J15") (pin "22") (pinfunction "22_22") (pintype "passive"))
      (node (ref "J6") (pin "1") (pinfunction "1_1") (pintype "passive"))
      (node (ref "J7") (pin "1") (pinfunction "1_1") (pintype "passive"))
      (node (ref "R11") (pin "8") (pinfunction "8_8") (pintype "passive"))
      (node (ref "U1") (pin "26") (pinfunction "PA17_26") (pintype "bidirectional"))
    )
    (net (code "67") (name "SCL2") (class "Default")
      (node (ref "J16") (pin "P$2") (pinfunction "2_P$2") (pintype "passive"))
      (node (ref "R11") (pin "5") (pinfunction "5_5") (pintype "passive"))
      (node (ref "U1") (pin "22") (pinfunction "PA13_22") (pintype "bidirectional"))
      (node (ref "U4") (pin "23") (pinfunction "SCL_23") (pintype "input"))
    )
    (net (code "68") (name "SDA1") (class "Default")
      (node (ref "J15") (pin "23") (pinfunction "23_23") (pintype "passive"))
      (node (ref "J15") (pin "24") (pinfunction "24_24") (pintype "passive"))
      (node (ref "J6") (pin "2") (pinfunction "2_2") (pintype "passive"))
      (node (ref "J7") (pin "2") (pinfunction "2_2") (pintype "passive"))
      (node (ref "R11") (pin "7") (pinfunction "7_7") (pintype "passive"))
      (node (ref "U1") (pin "25") (pinfunction "PA16_25") (pintype "bidirectional"))
    )
    (net (code "69") (name "SDA2") (class "Default")
      (node (ref "J16") (pin "P$3") (pinfunction "3_P$3") (pintype "passive"))
      (node (ref "R11") (pin "6") (pinfunction "6_6") (pintype "passive"))
      (node (ref "U1") (pin "21") (pinfunction "PA12_21") (pintype "bidirectional"))
      (node (ref "U4") (pin "24") (pinfunction "SDA_24") (pintype "bidirectional"))
    )
    (net (code "70") (name "SERVO1") (class "Default")
      (node (ref "J12") (pin "1") (pinfunction "1_1") (pintype "passive"))
      (node (ref "U1") (pin "2") (pinfunction "PA01_2") (pintype "bidirectional"))
    )
    (net (code "71") (name "SERVO2") (class "Default")
      (node (ref "J12") (pin "4") (pinfunction "4_4") (pintype "passive"))
      (node (ref "U1") (pin "1") (pinfunction "PA00_1") (pintype "bidirectional"))
    )
    (net (code "72") (name "SERVO3") (class "Default")
      (node (ref "J12") (pin "7") (pinfunction "7_7") (pintype "passive"))
      (node (ref "U1") (pin "13") (pinfunction "PA08_13") (pintype "bidirectional"))
    )
    (net (code "73") (name "SERVO4") (class "Default")
      (node (ref "J12") (pin "10") (pinfunction "10_10") (pintype "passive"))
      (node (ref "U1") (pin "14") (pinfunction "PA09_14") (pintype "bidirectional"))
    )
    (net (code "74") (name "SONAR1ECHO") (class "Default")
      (node (ref "U1") (pin "41") (pinfunction "PA28_41") (pintype "bidirectional"))
      (node (ref "U7") (pin "5") (pinfunction "A4_5") (pintype "bidirectional"))
    )
    (net (code "75") (name "SONAR1TRIG") (class "Default")
      (node (ref "J10") (pin "2") (pinfunction "2_2") (pintype "passive"))
      (node (ref "U1") (pin "39") (pinfunction "PA27_39") (pintype "bidirectional"))
    )
    (net (code "76") (name "SONAR2ECHO") (class "Default")
      (node (ref "U1") (pin "47") (pinfunction "PB02_47") (pintype "bidirectional"))
      (node (ref "U7") (pin "4") (pinfunction "A3_4") (pintype "bidirectional"))
    )
    (net (code "77") (name "SONAR2TRIG") (class "Default")
      (node (ref "J9") (pin "2") (pinfunction "2_2") (pintype "passive"))
      (node (ref "U1") (pin "38") (pinfunction "PB23_38") (pintype "bidirectional"))
    )
    (net (code "78") (name "SONAR3ECHO") (class "Default")
      (node (ref "U1") (pin "48") (pinfunction "PB03_48") (pintype "bidirectional"))
      (node (ref "U7") (pin "3") (pinfunction "A2_3") (pintype "bidirectional"))
    )
    (net (code "79") (name "SONAR3TRIG") (class "Default")
      (node (ref "J8") (pin "2") (pinfunction "2_2") (pintype "passive"))
      (node (ref "U1") (pin "37") (pinfunction "PB22_37") (pintype "bidirectional"))
    )
    (net (code "80") (name "SWCLK") (class "Default")
      (node (ref "R109") (pin "2") (pinfunction "2_2") (pintype "passive"))
      (node (ref "TP2") (pin "TP") (pinfunction "TP_TP") (pintype "input"))
      (node (ref "U1") (pin "45") (pinfunction "PA30_45") (pintype "bidirectional"))
    )
    (net (code "81") (name "SWDIO") (class "Default")
      (node (ref "TP3") (pin "TP") (pinfunction "TP_TP") (pintype "input"))
      (node (ref "U1") (pin "46") (pinfunction "PA31_46") (pintype "bidirectional"))
    )
    (net (code "82") (name "TX") (class "Default")
      (node (ref "J17") (pin "P$2") (pinfunction "2_P$2") (pintype "passive"))
      (node (ref "U1") (pin "19") (pinfunction "PB10_19") (pintype "bidirectional"))
    )
    (net (code "83") (name "VSENSE") (class "Default")
      (node (ref "R5") (pin "1") (pinfunction "1_1") (pintype "passive"))
      (node (ref "R6") (pin "1") (pinfunction "1_1") (pintype "passive"))
      (node (ref "U1") (pin "12") (pinfunction "PA07_12") (pintype "bidirectional"))
    )
    (net (code "84") (name "unconnected-(J15-Pad1)") (class "Default")
      (node (ref "J15") (pin "1") (pinfunction "1_1") (pintype "passive"))
    )
    (net (code "85") (name "unconnected-(J15-Pad5)") (class "Default")
      (node (ref "J15") (pin "5") (pinfunction "5_5") (pintype "passive"))
    )
    (net (code "86") (name "unconnected-(J17-4-PadP$4)") (class "Default")
      (node (ref "J17") (pin "P$4") (pinfunction "4_P$4") (pintype "passive"))
    )
    (net (code "87") (name "unconnected-(J17-5-PadP$5)") (class "Default")
      (node (ref "J17") (pin "P$5") (pinfunction "5_P$5") (pintype "passive"))
    )
    (net (code "88") (name "unconnected-(U1-PA03-Pad4)") (class "Default")
      (node (ref "U1") (pin "4") (pinfunction "PA03_4") (pintype "bidirectional"))
    )
    (net (code "89") (name "unconnected-(U1-PA11-Pad16)") (class "Default")
      (node (ref "U1") (pin "16") (pinfunction "PA11_16") (pintype "bidirectional"))
    )
    (net (code "90") (name "unconnected-(U4-AUX_CL-Pad7)") (class "Default")
      (node (ref "U4") (pin "7") (pinfunction "AUX_CL_7") (pintype "input"))
    )
    (net (code "91") (name "unconnected-(U4-AUX_DA-Pad6)") (class "Default")
      (node (ref "U4") (pin "6") (pinfunction "AUX_DA_6") (pintype "bidirectional"))
    )
    (net (code "92") (name "unconnected-(U4-INT-Pad12)") (class "Default")
      (node (ref "U4") (pin "12") (pinfunction "INT_12") (pintype "output"))
    )
    (net (code "93") (name "unconnected-(U4-RESV-Pad19)") (class "Default")
      (node (ref "U4") (pin "19") (pinfunction "RESV_19") (pintype "passive"))
    )
    (net (code "94") (name "unconnected-(U4-RESV-Pad21)") (class "Default")
      (node (ref "U4") (pin "21") (pinfunction "RESV_21") (pintype "passive"))
    )
    (net (code "95") (name "unconnected-(U4-RESV-Pad22)") (class "Default")
      (node (ref "U4") (pin "22") (pinfunction "RESV_22") (pintype "passive"))
    )
    (net (code "96") (name "unconnected-(U7-A1-Pad2)") (class "Default")
      (node (ref "U7") (pin "2") (pinfunction "A1_2") (pintype "bidirectional"))
    )
    (net (code "97") (name "unconnected-(U7-B1-Pad13)") (class "Default")
      (node (ref "U7") (pin "13") (pinfunction "B1_13") (pintype "bidirectional"))
    )
    (net (code "98") (name "unconnected-(U7-NC-Pad9)") (class "Default")
      (node (ref "U7") (pin "9") (pinfunction "NC_9") (pintype "no_connect"))
    )
    (net (code "99") (name "unconnected-(U7-NC_2-Pad6)") (class "Default")
      (node (ref "U7") (pin "6") (pinfunction "NC_2_6") (pintype "no_connect"))
    )
    (net (code "100") (name "unconnected-(USB1-ID-Pad4)") (class "Default")
      (node (ref "USB1") (pin "4") (pinfunction "ID_4") (pintype "bidirectional"))
    )
    (net (code "101") (name "unconnected-(USB1-VCC-Pad1)") (class "Default")
      (node (ref "USB1") (pin "1") (pinfunction "VCC_1") (pintype "bidirectional"))
    )
    (net (code "102") (name "~{RESET}") (class "Default")
      (node (ref "C14") (pin "1") (pinfunction "1_1") (pintype "passive"))
      (node (ref "J14") (pin "1") (pinfunction "1_1") (pintype "passive"))
      (node (ref "J14") (pin "2") (pinfunction "2_2") (pintype "passive"))
      (node (ref "R10") (pin "2") (pinfunction "2_2") (pintype "passive"))
      (node (ref "TP1") (pin "TP") (pinfunction "TP_TP") (pintype "input"))
      (node (ref "U1") (pin "40") (pinfunction "RSTN_40") (pintype "bidirectional"))
    )
  )
)
